# Private_CPU_Sub_Power_Supplies.net
KiCad netlist of a schematic drawn in Altium Designer
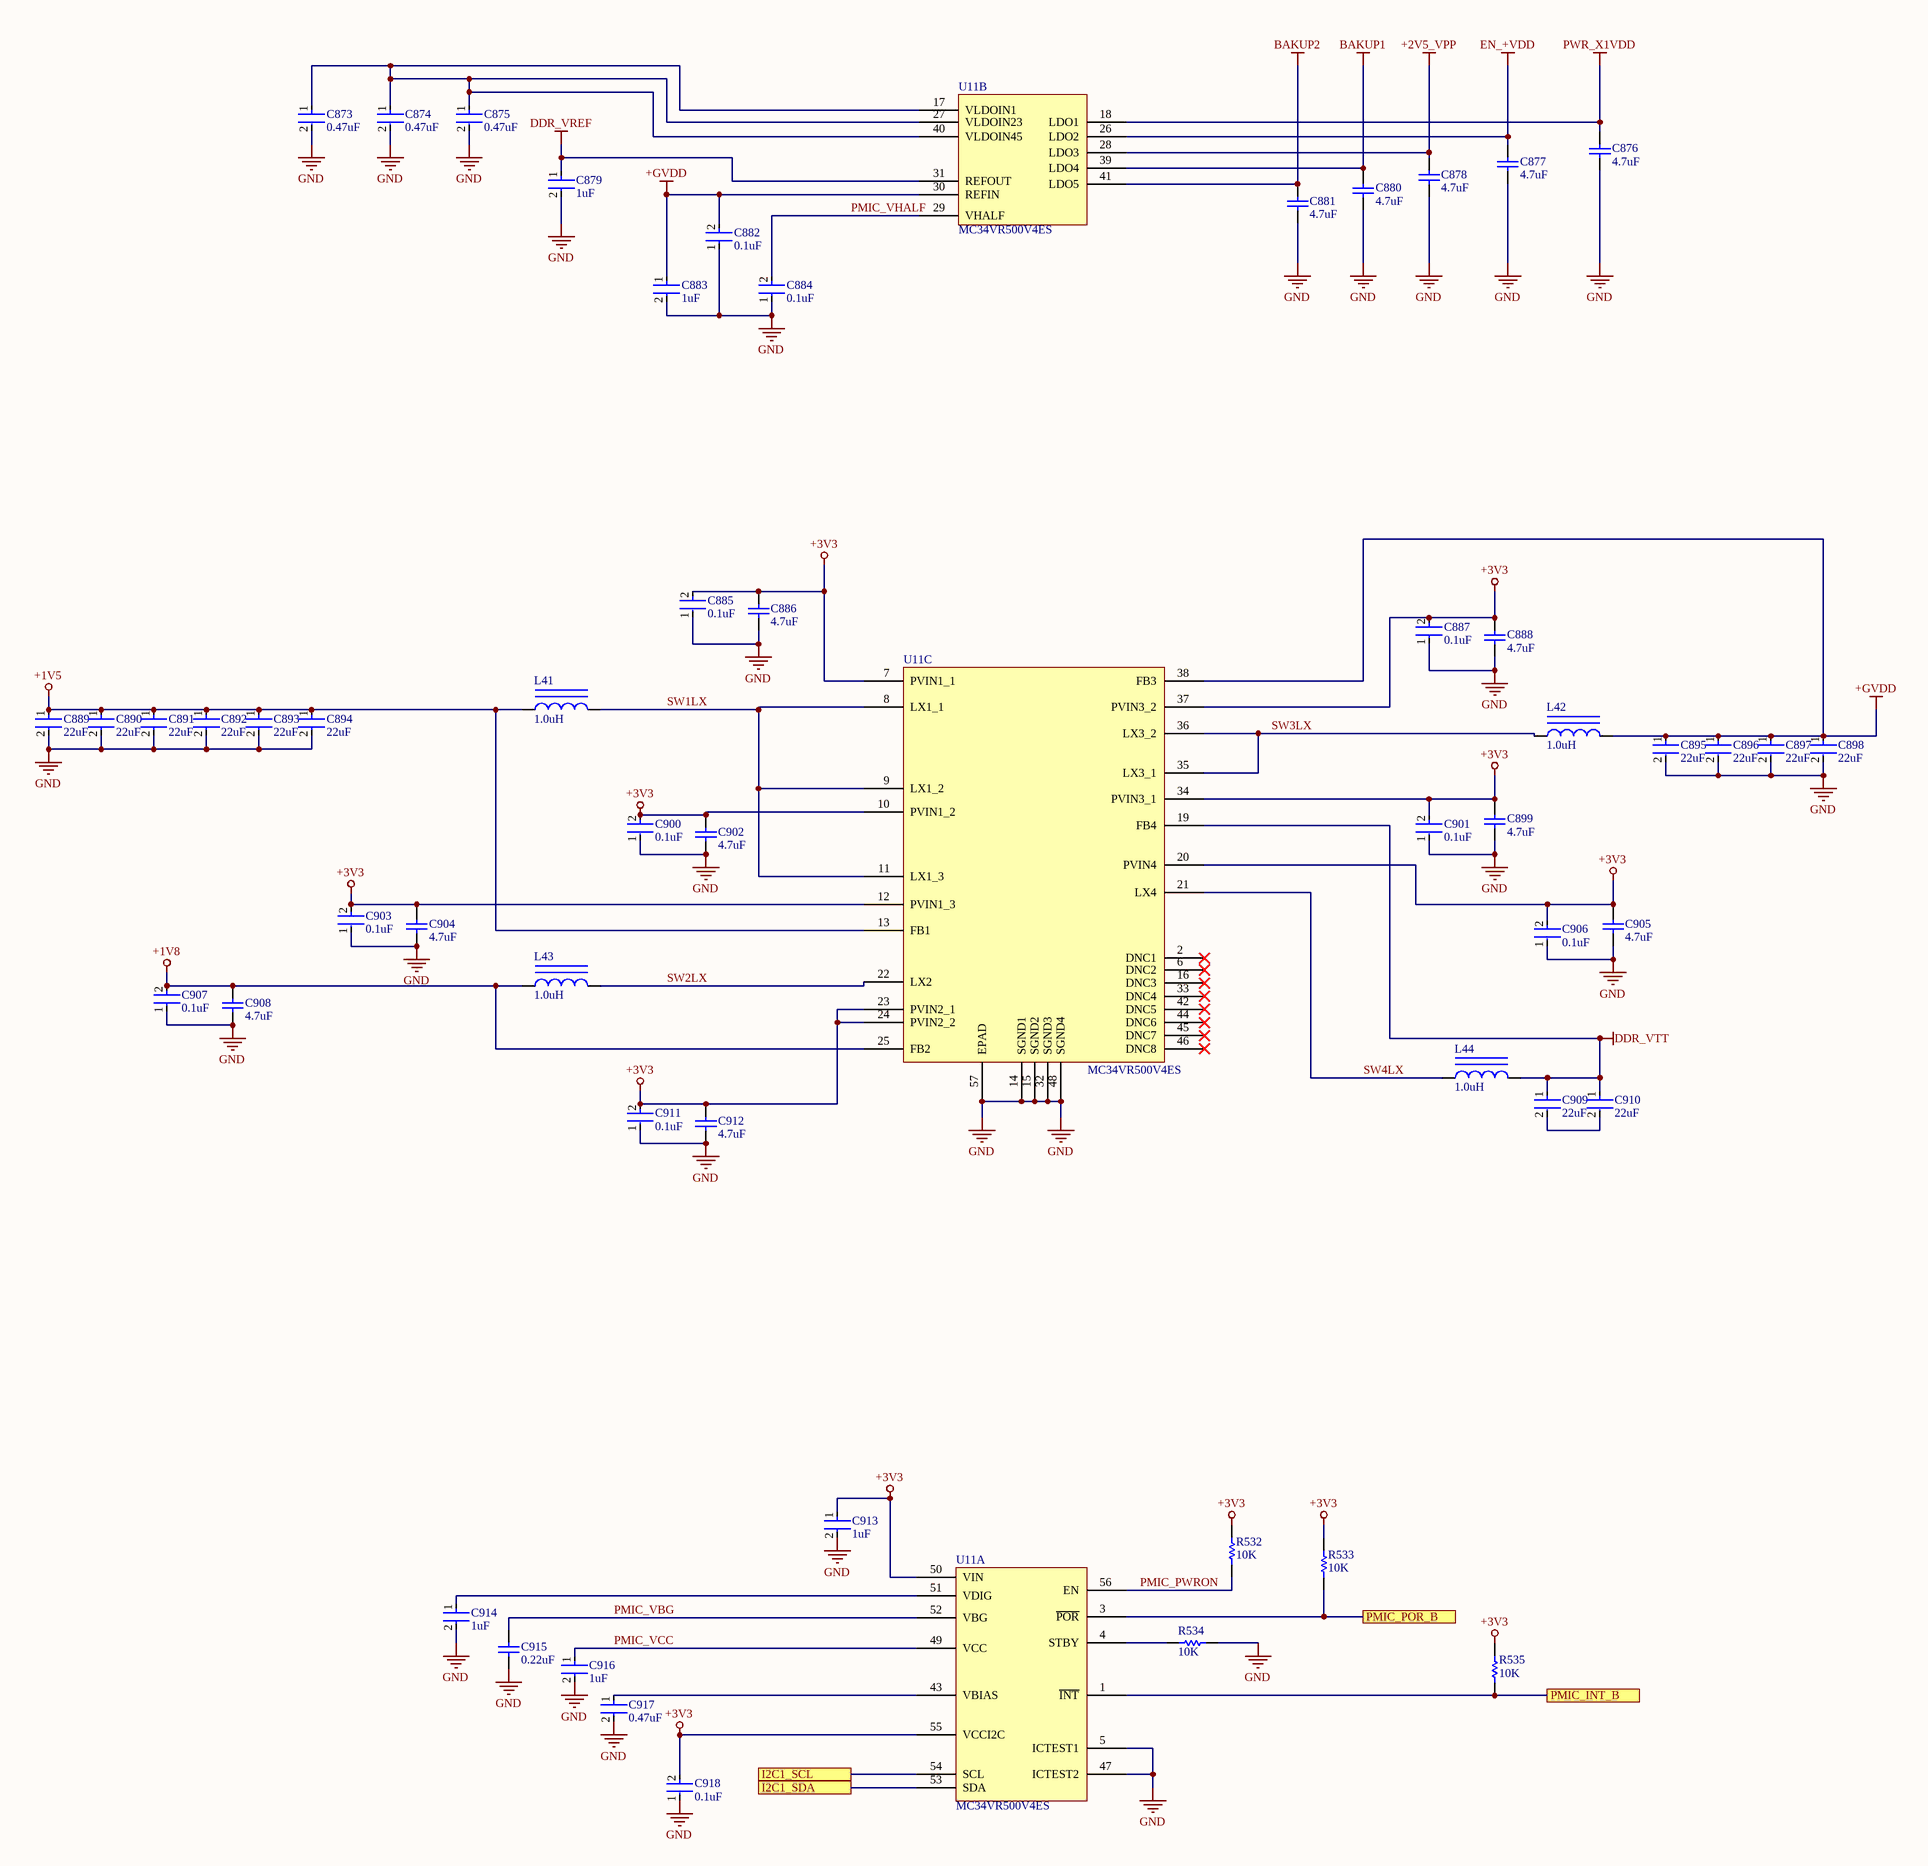
[diagram p0: Private_CPU_Sub_Power_Supplies.SchDoc]

(export (version "E")
  (design (tool "Eeschema 10.0.6"))
  (components
    (comp (ref "C873")
      (value "0.47uF")
      (footprint "FP-GRM188-0_1-e0_2_0_5-IPC_B")
      (description "Chip Multilayer Ceramic Capacitors for General Purpose, 0603, 0.47uF, X7R, 15%, 10%, 16V")
      (fields (field (name "VOLTAGE") "16V") (field (name "TOLERANCE") "10%"))
      (libsource (lib "Altium Content Vault") (part "11868f565c42a9108669ba33697ecf6"))
    )
    (comp (ref "C874")
      (value "0.47uF")
      (footprint "FP-GRM188-0_1-e0_2_0_5-IPC_B")
      (description "Chip Multilayer Ceramic Capacitors for General Purpose, 0603, 0.47uF, X7R, 15%, 10%, 16V")
      (fields (field (name "VOLTAGE") "16V") (field (name "TOLERANCE") "10%"))
      (libsource (lib "Altium Content Vault") (part "11868f565c42a9108669ba33697ecf6"))
    )
    (comp (ref "C875")
      (value "0.47uF")
      (footprint "FP-GRM188-0_1-e0_2_0_5-IPC_B")
      (description "Chip Multilayer Ceramic Capacitors for General Purpose, 0603, 0.47uF, X7R, 15%, 10%, 16V")
      (fields (field (name "VOLTAGE") "16V") (field (name "TOLERANCE") "10%"))
      (libsource (lib "Altium Content Vault") (part "11868f565c42a9108669ba33697ecf6"))
    )
    (comp (ref "C876")
      (value "4.7uF")
      (footprint "CAPC2013X145X50ML20T25")
      (fields (field (name "MANUFACTURER") "Kemet") (field (name "PART NUMBER") "C0805C475K3PACTU"))
      (libsource (lib "Altium Content Vault") (part "CAP"))
    )
    (comp (ref "C877")
      (value "4.7uF")
      (footprint "CAPC2013X145X50ML20T25")
      (fields (field (name "MANUFACTURER") "Kemet") (field (name "PART NUMBER") "C0805C475K3PACTU"))
      (libsource (lib "Altium Content Vault") (part "CAP"))
    )
    (comp (ref "C878")
      (value "4.7uF")
      (footprint "CAPC2013X145X50ML20T25")
      (fields (field (name "MANUFACTURER") "Kemet") (field (name "PART NUMBER") "C0805C475K3PACTU"))
      (libsource (lib "Altium Content Vault") (part "CAP"))
    )
    (comp (ref "C879")
      (value "1uF")
      (footprint "FP-GRM15-0_1-MFG")
      (description "CAP CER 1UF 10V X5R 0402")
      (fields
        (field (name "OCTOPART") "https://octopart.com/grm155r61a105ke15d-murata-197442")
        (field (name "MANUFACTURER PART NUMBER") "GRM155R61A105KE15D")
      )
      (libsource (lib "Altium Content Vault") (part "02cd4be3c70576c341d710602a673aa"))
    )
    (comp (ref "C880")
      (value "4.7uF")
      (footprint "CAPC2013X145X50ML20T25")
      (fields (field (name "MANUFACTURER") "Kemet") (field (name "PART NUMBER") "C0805C475K3PACTU"))
      (libsource (lib "Altium Content Vault") (part "CAP"))
    )
    (comp (ref "C881")
      (value "4.7uF")
      (footprint "CAPC2013X145X50ML20T25")
      (fields (field (name "MANUFACTURER") "Kemet") (field (name "PART NUMBER") "C0805C475K3PACTU"))
      (libsource (lib "Altium Content Vault") (part "CAP"))
    )
    (comp (ref "C882")
      (value "0.1uF")
      (footprint "FP-GRM15-MFG")
      (description "CAP CER 0.1UF 16V X7R 0402")
      (fields (field (name "MANUFACTURER PART NUMBER") "GRM155R71C104KA88D") (field (name "TOLERANCE") "10%"))
      (libsource (lib "Altium Content Vault") (part "236180d848d6139a670b325ea6854c9"))
    )
    (comp (ref "C883")
      (value "1uF")
      (footprint "FP-GRM15-0_1-MFG")
      (description "CAP CER 1UF 10V X5R 0402")
      (fields
        (field (name "OCTOPART") "https://octopart.com/grm155r61a105ke15d-murata-197442")
        (field (name "MANUFACTURER PART NUMBER") "GRM155R61A105KE15D")
      )
      (libsource (lib "Altium Content Vault") (part "02cd4be3c70576c341d710602a673aa"))
    )
    (comp (ref "C884")
      (value "0.1uF")
      (footprint "FP-GRM15-MFG")
      (description "CAP CER 0.1UF 16V X7R 0402")
      (fields (field (name "MANUFACTURER PART NUMBER") "GRM155R71C104KA88D") (field (name "TOLERANCE") "10%"))
      (libsource (lib "Altium Content Vault") (part "236180d848d6139a670b325ea6854c9"))
    )
    (comp (ref "C885")
      (value "0.1uF")
      (footprint "FP-GRM15-MFG")
      (description "CAP CER 0.1UF 16V X7R 0402")
      (fields (field (name "MANUFACTURER PART NUMBER") "GRM155R71C104KA88D") (field (name "TOLERANCE") "10%"))
      (libsource (lib "Altium Content Vault") (part "236180d848d6139a670b325ea6854c9"))
    )
    (comp (ref "C886")
      (value "4.7uF")
      (footprint "CAPC2013X145X50ML20T25")
      (fields (field (name "MANUFACTURER") "Kemet") (field (name "PART NUMBER") "C0805C475K3PACTU"))
      (libsource (lib "Altium Content Vault") (part "CAP"))
    )
    (comp (ref "C887")
      (value "0.1uF")
      (footprint "FP-GRM15-MFG")
      (description "CAP CER 0.1UF 16V X7R 0402")
      (fields (field (name "MANUFACTURER PART NUMBER") "GRM155R71C104KA88D") (field (name "TOLERANCE") "10%"))
      (libsource (lib "Altium Content Vault") (part "236180d848d6139a670b325ea6854c9"))
    )
    (comp (ref "C888")
      (value "4.7uF")
      (footprint "CAPC2013X145X50ML20T25")
      (fields (field (name "MANUFACTURER") "Kemet") (field (name "PART NUMBER") "C0805C475K3PACTU"))
      (libsource (lib "Altium Content Vault") (part "CAP"))
    )
    (comp (ref "C889")
      (value "22uF")
      (footprint "FP-GRM21B-0_15-MFG")
      (description "Chip Multilayer Ceramic Capacitors for General Purpose, 0805, 22uF, X5R, 15%, 20%, 6.3V")
      (fields (field (name "VOLTAGE") "6.3V") (field (name "TOLERANCE") "20%"))
      (libsource (lib "Altium Content Vault") (part "b4654b650e69147ec39a6b967a45e02"))
    )
    (comp (ref "C890")
      (value "22uF")
      (footprint "FP-GRM21B-0_15-MFG")
      (description "Chip Multilayer Ceramic Capacitors for General Purpose, 0805, 22uF, X5R, 15%, 20%, 6.3V")
      (fields (field (name "VOLTAGE") "6.3V") (field (name "TOLERANCE") "20%"))
      (libsource (lib "Altium Content Vault") (part "b4654b650e69147ec39a6b967a45e02"))
    )
    (comp (ref "C891")
      (value "22uF")
      (footprint "FP-GRM21B-0_15-MFG")
      (description "Chip Multilayer Ceramic Capacitors for General Purpose, 0805, 22uF, X5R, 15%, 20%, 6.3V")
      (fields (field (name "VOLTAGE") "6.3V") (field (name "TOLERANCE") "20%"))
      (libsource (lib "Altium Content Vault") (part "b4654b650e69147ec39a6b967a45e02"))
    )
    (comp (ref "C892")
      (value "22uF")
      (footprint "FP-GRM21B-0_15-MFG")
      (description "Chip Multilayer Ceramic Capacitors for General Purpose, 0805, 22uF, X5R, 15%, 20%, 6.3V")
      (fields (field (name "VOLTAGE") "6.3V") (field (name "TOLERANCE") "20%"))
      (libsource (lib "Altium Content Vault") (part "b4654b650e69147ec39a6b967a45e02"))
    )
    (comp (ref "C893")
      (value "22uF")
      (footprint "FP-GRM21B-0_15-MFG")
      (description "Chip Multilayer Ceramic Capacitors for General Purpose, 0805, 22uF, X5R, 15%, 20%, 6.3V")
      (fields (field (name "VOLTAGE") "6.3V") (field (name "TOLERANCE") "20%"))
      (libsource (lib "Altium Content Vault") (part "b4654b650e69147ec39a6b967a45e02"))
    )
    (comp (ref "C894")
      (value "22uF")
      (footprint "FP-GRM21B-0_15-MFG")
      (description "Chip Multilayer Ceramic Capacitors for General Purpose, 0805, 22uF, X5R, 15%, 20%, 6.3V")
      (fields (field (name "VOLTAGE") "6.3V") (field (name "TOLERANCE") "20%"))
      (libsource (lib "Altium Content Vault") (part "b4654b650e69147ec39a6b967a45e02"))
    )
    (comp (ref "C895")
      (value "22uF")
      (footprint "FP-GRM21B-0_15-MFG")
      (description "Chip Multilayer Ceramic Capacitors for General Purpose, 0805, 22uF, X5R, 15%, 20%, 6.3V")
      (fields (field (name "VOLTAGE") "6.3V") (field (name "TOLERANCE") "20%"))
      (libsource (lib "Altium Content Vault") (part "b4654b650e69147ec39a6b967a45e02"))
    )
    (comp (ref "C896")
      (value "22uF")
      (footprint "FP-GRM21B-0_15-MFG")
      (description "Chip Multilayer Ceramic Capacitors for General Purpose, 0805, 22uF, X5R, 15%, 20%, 6.3V")
      (fields (field (name "VOLTAGE") "6.3V") (field (name "TOLERANCE") "20%"))
      (libsource (lib "Altium Content Vault") (part "b4654b650e69147ec39a6b967a45e02"))
    )
    (comp (ref "C897")
      (value "22uF")
      (footprint "FP-GRM21B-0_15-MFG")
      (description "Chip Multilayer Ceramic Capacitors for General Purpose, 0805, 22uF, X5R, 15%, 20%, 6.3V")
      (fields (field (name "VOLTAGE") "6.3V") (field (name "TOLERANCE") "20%"))
      (libsource (lib "Altium Content Vault") (part "b4654b650e69147ec39a6b967a45e02"))
    )
    (comp (ref "C898")
      (value "22uF")
      (footprint "FP-GRM21B-0_15-MFG")
      (description "Chip Multilayer Ceramic Capacitors for General Purpose, 0805, 22uF, X5R, 15%, 20%, 6.3V")
      (fields (field (name "VOLTAGE") "6.3V") (field (name "TOLERANCE") "20%"))
      (libsource (lib "Altium Content Vault") (part "b4654b650e69147ec39a6b967a45e02"))
    )
    (comp (ref "C899")
      (value "4.7uF")
      (footprint "CAPC2013X145X50ML20T25")
      (fields (field (name "MANUFACTURER") "Kemet") (field (name "PART NUMBER") "C0805C475K3PACTU"))
      (libsource (lib "Altium Content Vault") (part "CAP"))
    )
    (comp (ref "C900")
      (value "0.1uF")
      (footprint "FP-GRM15-MFG")
      (description "CAP CER 0.1UF 16V X7R 0402")
      (fields (field (name "MANUFACTURER PART NUMBER") "GRM155R71C104KA88D") (field (name "TOLERANCE") "10%"))
      (libsource (lib "Altium Content Vault") (part "236180d848d6139a670b325ea6854c9"))
    )
    (comp (ref "C901")
      (value "0.1uF")
      (footprint "FP-GRM15-MFG")
      (description "CAP CER 0.1UF 16V X7R 0402")
      (fields (field (name "MANUFACTURER PART NUMBER") "GRM155R71C104KA88D") (field (name "TOLERANCE") "10%"))
      (libsource (lib "Altium Content Vault") (part "236180d848d6139a670b325ea6854c9"))
    )
    (comp (ref "C902")
      (value "4.7uF")
      (footprint "CAPC2013X145X50ML20T25")
      (fields (field (name "MANUFACTURER") "Kemet") (field (name "PART NUMBER") "C0805C475K3PACTU"))
      (libsource (lib "Altium Content Vault") (part "CAP"))
    )
    (comp (ref "C903")
      (value "0.1uF")
      (footprint "FP-GRM15-MFG")
      (description "CAP CER 0.1UF 16V X7R 0402")
      (fields (field (name "MANUFACTURER PART NUMBER") "GRM155R71C104KA88D") (field (name "TOLERANCE") "10%"))
      (libsource (lib "Altium Content Vault") (part "236180d848d6139a670b325ea6854c9"))
    )
    (comp (ref "C904")
      (value "4.7uF")
      (footprint "CAPC2013X145X50ML20T25")
      (fields (field (name "MANUFACTURER") "Kemet") (field (name "PART NUMBER") "C0805C475K3PACTU"))
      (libsource (lib "Altium Content Vault") (part "CAP"))
    )
    (comp (ref "C905")
      (value "4.7uF")
      (footprint "CAPC2013X145X50ML20T25")
      (fields (field (name "MANUFACTURER") "Kemet") (field (name "PART NUMBER") "C0805C475K3PACTU"))
      (libsource (lib "Altium Content Vault") (part "CAP"))
    )
    (comp (ref "C906")
      (value "0.1uF")
      (footprint "FP-GRM15-MFG")
      (description "CAP CER 0.1UF 16V X7R 0402")
      (fields (field (name "MANUFACTURER PART NUMBER") "GRM155R71C104KA88D") (field (name "TOLERANCE") "10%"))
      (libsource (lib "Altium Content Vault") (part "236180d848d6139a670b325ea6854c9"))
    )
    (comp (ref "C907")
      (value "0.1uF")
      (footprint "FP-GRM15-MFG")
      (description "CAP CER 0.1UF 16V X7R 0402")
      (fields (field (name "MANUFACTURER PART NUMBER") "GRM155R71C104KA88D") (field (name "TOLERANCE") "10%"))
      (libsource (lib "Altium Content Vault") (part "236180d848d6139a670b325ea6854c9"))
    )
    (comp (ref "C908")
      (value "4.7uF")
      (footprint "CAPC2013X145X50ML20T25")
      (fields (field (name "MANUFACTURER") "Kemet") (field (name "PART NUMBER") "C0805C475K3PACTU"))
      (libsource (lib "Altium Content Vault") (part "CAP"))
    )
    (comp (ref "C909")
      (value "22uF")
      (footprint "FP-GRM21B-0_15-MFG")
      (description "Chip Multilayer Ceramic Capacitors for General Purpose, 0805, 22uF, X5R, 15%, 20%, 6.3V")
      (fields (field (name "VOLTAGE") "6.3V") (field (name "TOLERANCE") "20%"))
      (libsource (lib "Altium Content Vault") (part "b4654b650e69147ec39a6b967a45e02"))
    )
    (comp (ref "C910")
      (value "22uF")
      (footprint "FP-GRM21B-0_15-MFG")
      (description "Chip Multilayer Ceramic Capacitors for General Purpose, 0805, 22uF, X5R, 15%, 20%, 6.3V")
      (fields (field (name "VOLTAGE") "6.3V") (field (name "TOLERANCE") "20%"))
      (libsource (lib "Altium Content Vault") (part "b4654b650e69147ec39a6b967a45e02"))
    )
    (comp (ref "C911")
      (value "0.1uF")
      (footprint "FP-GRM15-MFG")
      (description "CAP CER 0.1UF 16V X7R 0402")
      (fields (field (name "MANUFACTURER PART NUMBER") "GRM155R71C104KA88D") (field (name "TOLERANCE") "10%"))
      (libsource (lib "Altium Content Vault") (part "236180d848d6139a670b325ea6854c9"))
    )
    (comp (ref "C912")
      (value "4.7uF")
      (footprint "CAPC2013X145X50ML20T25")
      (fields (field (name "MANUFACTURER") "Kemet") (field (name "PART NUMBER") "C0805C475K3PACTU"))
      (libsource (lib "Altium Content Vault") (part "CAP"))
    )
    (comp (ref "C913")
      (value "1uF")
      (footprint "FP-GRM15-0_1-MFG")
      (description "CAP CER 1UF 10V X5R 0402")
      (fields
        (field (name "OCTOPART") "https://octopart.com/grm155r61a105ke15d-murata-197442")
        (field (name "MANUFACTURER PART NUMBER") "GRM155R61A105KE15D")
      )
      (libsource (lib "Altium Content Vault") (part "02cd4be3c70576c341d710602a673aa"))
    )
    (comp (ref "C914")
      (value "1uF")
      (footprint "FP-GRM15-0_1-MFG")
      (description "CAP CER 1UF 10V X5R 0402")
      (fields
        (field (name "OCTOPART") "https://octopart.com/grm155r61a105ke15d-murata-197442")
        (field (name "MANUFACTURER PART NUMBER") "GRM155R61A105KE15D")
      )
      (libsource (lib "Altium Content Vault") (part "02cd4be3c70576c341d710602a673aa"))
    )
    (comp (ref "C915")
      (value "0.22uF")
      (footprint "CAPC1005X55X25NL05T10")
      (description "Chip Capacitor, 220 nF, +/- 10%, 10 V, -55 to 85 degC, 0402 (1005 Metric), RoHS, Tape and Reel")
      (fields (field (name "MANUFACTURER") "Basic Passives") (field (name "TOLERANCE") "10%"))
      (libsource (lib "Altium Content Vault") (part "CAP-NP-2"))
    )
    (comp (ref "C916")
      (value "1uF")
      (footprint "FP-GRM15-0_1-MFG")
      (description "CAP CER 1UF 10V X5R 0402")
      (fields
        (field (name "OCTOPART") "https://octopart.com/grm155r61a105ke15d-murata-197442")
        (field (name "MANUFACTURER PART NUMBER") "GRM155R61A105KE15D")
      )
      (libsource (lib "Altium Content Vault") (part "02cd4be3c70576c341d710602a673aa"))
    )
    (comp (ref "C917")
      (value "0.47uF")
      (footprint "FP-GRM188-0_1-e0_2_0_5-IPC_B")
      (description "Chip Multilayer Ceramic Capacitors for General Purpose, 0603, 0.47uF, X7R, 15%, 10%, 16V")
      (fields (field (name "VOLTAGE") "16V") (field (name "TOLERANCE") "10%"))
      (libsource (lib "Altium Content Vault") (part "11868f565c42a9108669ba33697ecf6"))
    )
    (comp (ref "C918")
      (value "0.1uF")
      (footprint "FP-GRM15-MFG")
      (description "CAP CER 0.1UF 16V X7R 0402")
      (fields (field (name "MANUFACTURER PART NUMBER") "GRM155R71C104KA88D") (field (name "TOLERANCE") "10%"))
      (libsource (lib "Altium Content Vault") (part "236180d848d6139a670b325ea6854c9"))
    )
    (comp (ref "L41")
      (value "1.0uH")
      (footprint "BOUR-CM45_L")
      (description "Chip Inductor, 1 uH, +/- 10%, 450 mA, -40 to 125 degC, 2-Pin SMD (1812), RoHS, Tape and Reel")
      (fields (field (name "MANUFACTURER") "Bourns"))
      (libsource (lib "Altium Content Vault") (part "IND-IRON-2"))
    )
    (comp (ref "L42")
      (value "1.0uH")
      (footprint "BOUR-CM45_L")
      (description "Chip Inductor, 1 uH, +/- 10%, 450 mA, -40 to 125 degC, 2-Pin SMD (1812), RoHS, Tape and Reel")
      (fields (field (name "MANUFACTURER") "Bourns"))
      (libsource (lib "Altium Content Vault") (part "IND-IRON-2"))
    )
    (comp (ref "L43")
      (value "1.0uH")
      (footprint "BOUR-CM45_L")
      (description "Chip Inductor, 1 uH, +/- 10%, 450 mA, -40 to 125 degC, 2-Pin SMD (1812), RoHS, Tape and Reel")
      (fields (field (name "MANUFACTURER") "Bourns"))
      (libsource (lib "Altium Content Vault") (part "IND-IRON-2"))
    )
    (comp (ref "L44")
      (value "1.0uH")
      (footprint "BOUR-CM45_L")
      (description "Chip Inductor, 1 uH, +/- 10%, 450 mA, -40 to 125 degC, 2-Pin SMD (1812), RoHS, Tape and Reel")
      (fields (field (name "MANUFACTURER") "Bourns"))
      (libsource (lib "Altium Content Vault") (part "IND-IRON-2"))
    )
    (comp (ref "R532")
      (value "10K")
      (footprint "RESC1005X40X25LL05T05")
      (description "Chip Resistor, 10 KOhm, +/- 1%, 0.1 W, -55 to 155 degC, 0402 (1005 Metric), RoHS, Tape and Reel")
      (fields (field (name "TOLERANCE") "1%") (field (name "MANUFACTURER") "Panasonic"))
      (libsource (lib "Altium Content Vault") (part "RES-2"))
    )
    (comp (ref "R533")
      (value "10K")
      (footprint "RESC1005X40X25LL05T05")
      (description "Chip Resistor, 10 KOhm, +/- 1%, 0.1 W, -55 to 155 degC, 0402 (1005 Metric), RoHS, Tape and Reel")
      (fields (field (name "TOLERANCE") "1%") (field (name "MANUFACTURER") "Panasonic"))
      (libsource (lib "Altium Content Vault") (part "RES-2"))
    )
    (comp (ref "R534")
      (value "10K")
      (footprint "RESC1005X40X25LL05T05")
      (description "Chip Resistor, 10 KOhm, +/- 1%, 0.1 W, -55 to 155 degC, 0402 (1005 Metric), RoHS, Tape and Reel")
      (fields (field (name "TOLERANCE") "1%") (field (name "MANUFACTURER") "Panasonic"))
      (libsource (lib "Altium Content Vault") (part "RES-2"))
    )
    (comp (ref "R535")
      (value "10K")
      (footprint "RESC1005X40X25LL05T05")
      (description "Chip Resistor, 10 KOhm, +/- 1%, 0.1 W, -55 to 155 degC, 0402 (1005 Metric), RoHS, Tape and Reel")
      (fields (field (name "TOLERANCE") "1%") (field (name "MANUFACTURER") "Panasonic"))
      (libsource (lib "Altium Content Vault") (part "RES-2"))
    )
    (comp (ref "U11")
      (value "MC34VR500V4ES")
      (footprint "MC34VR500V4ES:QFN50P800X800X90-57N")
      (description "Regulator, Buck, Quad with up to 4.5A Output and Triple User-programmable LDOs, QFN 56, Tray")
      (fields (field (name "MF") "{'manufacturer': u'NXP Semiconductors'}"))
      (libsource (lib "MC34VR500V4ES") (part "MC34VR500V4ES"))
    )
  )
  (nets
    (net (code "1") (name "+1V5") (class "Default")
      (node (ref "C889") (pin "1") (pinfunction "1_1") (pintype "passive"))
      (node (ref "C890") (pin "1") (pinfunction "1_1") (pintype "passive"))
      (node (ref "C891") (pin "1") (pinfunction "1_1") (pintype "passive"))
      (node (ref "C892") (pin "1") (pinfunction "1_1") (pintype "passive"))
      (node (ref "C893") (pin "1") (pinfunction "1_1") (pintype "passive"))
      (node (ref "C894") (pin "1") (pinfunction "1_1") (pintype "passive"))
      (node (ref "L41") (pin "1") (pinfunction "1_1") (pintype "passive"))
      (node (ref "U11") (pin "13") (pinfunction "FB1_13") (pintype "passive"))
    )
    (net (code "2") (name "+1V8") (class "Default")
      (node (ref "C907") (pin "2") (pinfunction "2_2") (pintype "passive"))
      (node (ref "C908") (pin "2") (pinfunction "2_2") (pintype "passive"))
      (node (ref "L43") (pin "1") (pinfunction "1_1") (pintype "passive"))
      (node (ref "U11") (pin "25") (pinfunction "FB2_25") (pintype "passive"))
    )
    (net (code "3") (name "+2V5_VPP") (class "Default")
      (node (ref "C878") (pin "2") (pinfunction "2_2") (pintype "passive"))
      (node (ref "U11") (pin "28") (pinfunction "LDO3_28") (pintype "passive"))
    )
    (net (code "4") (name "+3V3") (class "Default")
      (node (ref "C885") (pin "2") (pinfunction "2_2") (pintype "passive"))
      (node (ref "C886") (pin "2") (pinfunction "2_2") (pintype "passive"))
      (node (ref "C887") (pin "2") (pinfunction "2_2") (pintype "passive"))
      (node (ref "C888") (pin "2") (pinfunction "2_2") (pintype "passive"))
      (node (ref "C899") (pin "2") (pinfunction "2_2") (pintype "passive"))
      (node (ref "C900") (pin "2") (pinfunction "2_2") (pintype "passive"))
      (node (ref "C901") (pin "2") (pinfunction "2_2") (pintype "passive"))
      (node (ref "C902") (pin "2") (pinfunction "2_2") (pintype "passive"))
      (node (ref "C903") (pin "2") (pinfunction "2_2") (pintype "passive"))
      (node (ref "C904") (pin "2") (pinfunction "2_2") (pintype "passive"))
      (node (ref "C905") (pin "2") (pinfunction "2_2") (pintype "passive"))
      (node (ref "C906") (pin "2") (pinfunction "2_2") (pintype "passive"))
      (node (ref "C911") (pin "2") (pinfunction "2_2") (pintype "passive"))
      (node (ref "C912") (pin "2") (pinfunction "2_2") (pintype "passive"))
      (node (ref "C913") (pin "1") (pinfunction "1_1") (pintype "passive"))
      (node (ref "C918") (pin "2") (pinfunction "2_2") (pintype "passive"))
      (node (ref "R532") (pin "2") (pinfunction "2_2") (pintype "passive"))
      (node (ref "R533") (pin "2") (pinfunction "2_2") (pintype "passive"))
      (node (ref "R535") (pin "2") (pinfunction "2_2") (pintype "passive"))
      (node (ref "U11") (pin "10") (pinfunction "PVIN1_2_10") (pintype "passive"))
      (node (ref "U11") (pin "12") (pinfunction "PVIN1_3_12") (pintype "passive"))
      (node (ref "U11") (pin "20") (pinfunction "PVIN4_20") (pintype "passive"))
      (node (ref "U11") (pin "23") (pinfunction "PVIN2_1_23") (pintype "passive"))
      (node (ref "U11") (pin "24") (pinfunction "PVIN2_2_24") (pintype "passive"))
      (node (ref "U11") (pin "34") (pinfunction "PVIN3_1_34") (pintype "passive"))
      (node (ref "U11") (pin "37") (pinfunction "PVIN3_2_37") (pintype "passive"))
      (node (ref "U11") (pin "50") (pinfunction "VIN_50") (pintype "passive"))
      (node (ref "U11") (pin "55") (pinfunction "VCCI2C_55") (pintype "passive"))
      (node (ref "U11") (pin "7") (pinfunction "PVIN1_1_7") (pintype "passive"))
    )
    (net (code "5") (name "+GVDD") (class "Default")
      (node (ref "C882") (pin "2") (pinfunction "2_2") (pintype "passive"))
      (node (ref "C883") (pin "1") (pinfunction "1_1") (pintype "passive"))
      (node (ref "C895") (pin "1") (pinfunction "1_1") (pintype "passive"))
      (node (ref "C896") (pin "1") (pinfunction "1_1") (pintype "passive"))
      (node (ref "C897") (pin "1") (pinfunction "1_1") (pintype "passive"))
      (node (ref "C898") (pin "1") (pinfunction "1_1") (pintype "passive"))
      (node (ref "L42") (pin "2") (pinfunction "2_2") (pintype "passive"))
      (node (ref "U11") (pin "30") (pinfunction "REFIN_30") (pintype "passive"))
      (node (ref "U11") (pin "38") (pinfunction "FB3_38") (pintype "passive"))
    )
    (net (code "6") (name "/I2C1_SCL") (class "Default")
      (node (ref "U11") (pin "54") (pinfunction "SCL_54") (pintype "passive"))
    )
    (net (code "7") (name "/I2C1_SDA") (class "Default")
      (node (ref "U11") (pin "53") (pinfunction "SDA_53") (pintype "passive"))
    )
    (net (code "8") (name "/PMIC_INT_B") (class "Default")
      (node (ref "R535") (pin "1") (pinfunction "1_1") (pintype "passive"))
      (node (ref "U11") (pin "1") (pinfunction "~{INT}_1") (pintype "passive"))
    )
    (net (code "9") (name "/PMIC_POR_B") (class "Default")
      (node (ref "R533") (pin "1") (pinfunction "1_1") (pintype "passive"))
      (node (ref "U11") (pin "3") (pinfunction "~{POR}_3") (pintype "passive"))
    )
    (net (code "10") (name "/PMIC_PWRON") (class "Default")
      (node (ref "R532") (pin "1") (pinfunction "1_1") (pintype "passive"))
      (node (ref "U11") (pin "56") (pinfunction "EN_56") (pintype "passive"))
    )
    (net (code "11") (name "/PMIC_VBG") (class "Default")
      (node (ref "C915") (pin "2") (pinfunction "2_2") (pintype "passive"))
      (node (ref "U11") (pin "52") (pinfunction "VBG_52") (pintype "passive"))
    )
    (net (code "12") (name "/PMIC_VCC") (class "Default")
      (node (ref "C916") (pin "1") (pinfunction "1_1") (pintype "passive"))
      (node (ref "U11") (pin "49") (pinfunction "VCC_49") (pintype "passive"))
    )
    (net (code "13") (name "/PMIC_VHALF") (class "Default")
      (node (ref "C884") (pin "2") (pinfunction "2_2") (pintype "passive"))
      (node (ref "U11") (pin "29") (pinfunction "VHALF_29") (pintype "passive"))
    )
    (net (code "14") (name "/SW1LX") (class "Default")
      (node (ref "L41") (pin "2") (pinfunction "2_2") (pintype "passive"))
      (node (ref "U11") (pin "11") (pinfunction "LX1_3_11") (pintype "passive"))
      (node (ref "U11") (pin "8") (pinfunction "LX1_1_8") (pintype "passive"))
      (node (ref "U11") (pin "9") (pinfunction "LX1_2_9") (pintype "passive"))
    )
    (net (code "15") (name "/SW2LX") (class "Default")
      (node (ref "L43") (pin "2") (pinfunction "2_2") (pintype "passive"))
      (node (ref "U11") (pin "22") (pinfunction "LX2_22") (pintype "passive"))
    )
    (net (code "16") (name "/SW3LX") (class "Default")
      (node (ref "L42") (pin "1") (pinfunction "1_1") (pintype "passive"))
      (node (ref "U11") (pin "35") (pinfunction "LX3_1_35") (pintype "passive"))
      (node (ref "U11") (pin "36") (pinfunction "LX3_2_36") (pintype "passive"))
    )
    (net (code "17") (name "/SW4LX") (class "Default")
      (node (ref "L44") (pin "1") (pinfunction "1_1") (pintype "passive"))
      (node (ref "U11") (pin "21") (pinfunction "LX4_21") (pintype "passive"))
    )
    (net (code "18") (name "BAKUP1") (class "Default")
      (node (ref "C880") (pin "2") (pinfunction "2_2") (pintype "passive"))
      (node (ref "U11") (pin "39") (pinfunction "LDO4_39") (pintype "passive"))
    )
    (net (code "19") (name "BAKUP2") (class "Default")
      (node (ref "C881") (pin "2") (pinfunction "2_2") (pintype "passive"))
      (node (ref "U11") (pin "41") (pinfunction "LDO5_41") (pintype "passive"))
    )
    (net (code "20") (name "DDR_VREF") (class "Default")
      (node (ref "C879") (pin "1") (pinfunction "1_1") (pintype "passive"))
      (node (ref "U11") (pin "31") (pinfunction "REFOUT_31") (pintype "passive"))
    )
    (net (code "21") (name "DDR_VTT") (class "Default")
      (node (ref "C909") (pin "1") (pinfunction "1_1") (pintype "passive"))
      (node (ref "C910") (pin "1") (pinfunction "1_1") (pintype "passive"))
      (node (ref "L44") (pin "2") (pinfunction "2_2") (pintype "passive"))
      (node (ref "U11") (pin "19") (pinfunction "FB4_19") (pintype "passive"))
    )
    (net (code "22") (name "EN_+VDD") (class "Default")
      (node (ref "C877") (pin "2") (pinfunction "2_2") (pintype "passive"))
      (node (ref "U11") (pin "26") (pinfunction "LDO2_26") (pintype "passive"))
    )
    (net (code "23") (name "GND") (class "Default")
      (node (ref "C873") (pin "2") (pinfunction "2_2") (pintype "passive"))
      (node (ref "C874") (pin "2") (pinfunction "2_2") (pintype "passive"))
      (node (ref "C875") (pin "2") (pinfunction "2_2") (pintype "passive"))
      (node (ref "C876") (pin "1") (pinfunction "1_1") (pintype "passive"))
      (node (ref "C877") (pin "1") (pinfunction "1_1") (pintype "passive"))
      (node (ref "C878") (pin "1") (pinfunction "1_1") (pintype "passive"))
      (node (ref "C879") (pin "2") (pinfunction "2_2") (pintype "passive"))
      (node (ref "C880") (pin "1") (pinfunction "1_1") (pintype "passive"))
      (node (ref "C881") (pin "1") (pinfunction "1_1") (pintype "passive"))
      (node (ref "C882") (pin "1") (pinfunction "1_1") (pintype "passive"))
      (node (ref "C883") (pin "2") (pinfunction "2_2") (pintype "passive"))
      (node (ref "C884") (pin "1") (pinfunction "1_1") (pintype "passive"))
      (node (ref "C885") (pin "1") (pinfunction "1_1") (pintype "passive"))
      (node (ref "C886") (pin "1") (pinfunction "1_1") (pintype "passive"))
      (node (ref "C887") (pin "1") (pinfunction "1_1") (pintype "passive"))
      (node (ref "C888") (pin "1") (pinfunction "1_1") (pintype "passive"))
      (node (ref "C889") (pin "2") (pinfunction "2_2") (pintype "passive"))
      (node (ref "C890") (pin "2") (pinfunction "2_2") (pintype "passive"))
      (node (ref "C891") (pin "2") (pinfunction "2_2") (pintype "passive"))
      (node (ref "C892") (pin "2") (pinfunction "2_2") (pintype "passive"))
      (node (ref "C893") (pin "2") (pinfunction "2_2") (pintype "passive"))
      (node (ref "C894") (pin "2") (pinfunction "2_2") (pintype "passive"))
      (node (ref "C895") (pin "2") (pinfunction "2_2") (pintype "passive"))
      (node (ref "C896") (pin "2") (pinfunction "2_2") (pintype "passive"))
      (node (ref "C897") (pin "2") (pinfunction "2_2") (pintype "passive"))
      (node (ref "C898") (pin "2") (pinfunction "2_2") (pintype "passive"))
      (node (ref "C899") (pin "1") (pinfunction "1_1") (pintype "passive"))
      (node (ref "C900") (pin "1") (pinfunction "1_1") (pintype "passive"))
      (node (ref "C901") (pin "1") (pinfunction "1_1") (pintype "passive"))
      (node (ref "C902") (pin "1") (pinfunction "1_1") (pintype "passive"))
      (node (ref "C903") (pin "1") (pinfunction "1_1") (pintype "passive"))
      (node (ref "C904") (pin "1") (pinfunction "1_1") (pintype "passive"))
      (node (ref "C905") (pin "1") (pinfunction "1_1") (pintype "passive"))
      (node (ref "C906") (pin "1") (pinfunction "1_1") (pintype "passive"))
      (node (ref "C907") (pin "1") (pinfunction "1_1") (pintype "passive"))
      (node (ref "C908") (pin "1") (pinfunction "1_1") (pintype "passive"))
      (node (ref "C911") (pin "1") (pinfunction "1_1") (pintype "passive"))
      (node (ref "C912") (pin "1") (pinfunction "1_1") (pintype "passive"))
      (node (ref "C913") (pin "2") (pinfunction "2_2") (pintype "passive"))
      (node (ref "C914") (pin "2") (pinfunction "2_2") (pintype "passive"))
      (node (ref "C915") (pin "1") (pinfunction "1_1") (pintype "passive"))
      (node (ref "C916") (pin "2") (pinfunction "2_2") (pintype "passive"))
      (node (ref "C917") (pin "2") (pinfunction "2_2") (pintype "passive"))
      (node (ref "C918") (pin "1") (pinfunction "1_1") (pintype "passive"))
      (node (ref "R534") (pin "1") (pinfunction "1_1") (pintype "passive"))
      (node (ref "U11") (pin "14") (pinfunction "SGND1_14") (pintype "passive"))
      (node (ref "U11") (pin "15") (pinfunction "SGND2_15") (pintype "passive"))
      (node (ref "U11") (pin "32") (pinfunction "SGND3_32") (pintype "passive"))
      (node (ref "U11") (pin "47") (pinfunction "ICTEST2_47") (pintype "passive"))
      (node (ref "U11") (pin "48") (pinfunction "SGND4_48") (pintype "passive"))
      (node (ref "U11") (pin "5") (pinfunction "ICTEST1_5") (pintype "passive"))
      (node (ref "U11") (pin "57") (pinfunction "EPAD_57") (pintype "passive"))
    )
    (net (code "24") (name "Net-(C909-Pad2)") (class "Default")
      (node (ref "C909") (pin "2") (pinfunction "2_2") (pintype "passive"))
      (node (ref "C910") (pin "2") (pinfunction "2_2") (pintype "passive"))
    )
    (net (code "25") (name "Net-(U11A-STBY)") (class "Default")
      (node (ref "R534") (pin "2") (pinfunction "2_2") (pintype "passive"))
      (node (ref "U11") (pin "4") (pinfunction "STBY_4") (pintype "passive"))
    )
    (net (code "26") (name "Net-(U11A-VBIAS)") (class "Default")
      (node (ref "C917") (pin "1") (pinfunction "1_1") (pintype "passive"))
      (node (ref "U11") (pin "43") (pinfunction "VBIAS_43") (pintype "passive"))
    )
    (net (code "27") (name "Net-(U11A-VDIG)") (class "Default")
      (node (ref "C914") (pin "1") (pinfunction "1_1") (pintype "passive"))
      (node (ref "U11") (pin "51") (pinfunction "VDIG_51") (pintype "passive"))
    )
    (net (code "28") (name "Net-(U11B-VLDOIN1)") (class "Default")
      (node (ref "C873") (pin "1") (pinfunction "1_1") (pintype "passive"))
      (node (ref "C874") (pin "1") (pinfunction "1_1") (pintype "passive"))
      (node (ref "C875") (pin "1") (pinfunction "1_1") (pintype "passive"))
      (node (ref "U11") (pin "17") (pinfunction "VLDOIN1_17") (pintype "passive"))
      (node (ref "U11") (pin "27") (pinfunction "VLDOIN23_27") (pintype "passive"))
      (node (ref "U11") (pin "40") (pinfunction "VLDOIN45_40") (pintype "passive"))
    )
    (net (code "29") (name "PWR_X1VDD") (class "Default")
      (node (ref "C876") (pin "2") (pinfunction "2_2") (pintype "passive"))
      (node (ref "U11") (pin "18") (pinfunction "LDO1_18") (pintype "passive"))
    )
    (net (code "30") (name "unconnected-(U11C-DNC1-Pad2)") (class "Default")
      (node (ref "U11") (pin "2") (pinfunction "DNC1_2") (pintype "passive+no_connect"))
    )
    (net (code "31") (name "unconnected-(U11C-DNC2-Pad6)") (class "Default")
      (node (ref "U11") (pin "6") (pinfunction "DNC2_6") (pintype "passive+no_connect"))
    )
    (net (code "32") (name "unconnected-(U11C-DNC3-Pad16)") (class "Default")
      (node (ref "U11") (pin "16") (pinfunction "DNC3_16") (pintype "passive+no_connect"))
    )
    (net (code "33") (name "unconnected-(U11C-DNC4-Pad33)") (class "Default")
      (node (ref "U11") (pin "33") (pinfunction "DNC4_33") (pintype "passive+no_connect"))
    )
    (net (code "34") (name "unconnected-(U11C-DNC5-Pad42)") (class "Default")
      (node (ref "U11") (pin "42") (pinfunction "DNC5_42") (pintype "passive+no_connect"))
    )
    (net (code "35") (name "unconnected-(U11C-DNC6-Pad44)") (class "Default")
      (node (ref "U11") (pin "44") (pinfunction "DNC6_44") (pintype "passive+no_connect"))
    )
    (net (code "36") (name "unconnected-(U11C-DNC7-Pad45)") (class "Default")
      (node (ref "U11") (pin "45") (pinfunction "DNC7_45") (pintype "passive+no_connect"))
    )
    (net (code "37") (name "unconnected-(U11C-DNC8-Pad46)") (class "Default")
      (node (ref "U11") (pin "46") (pinfunction "DNC8_46") (pintype "passive+no_connect"))
    )
  )
)
